# M10-4-20mA.net
KiCad netlist of a schematic drawn in Altium Designer
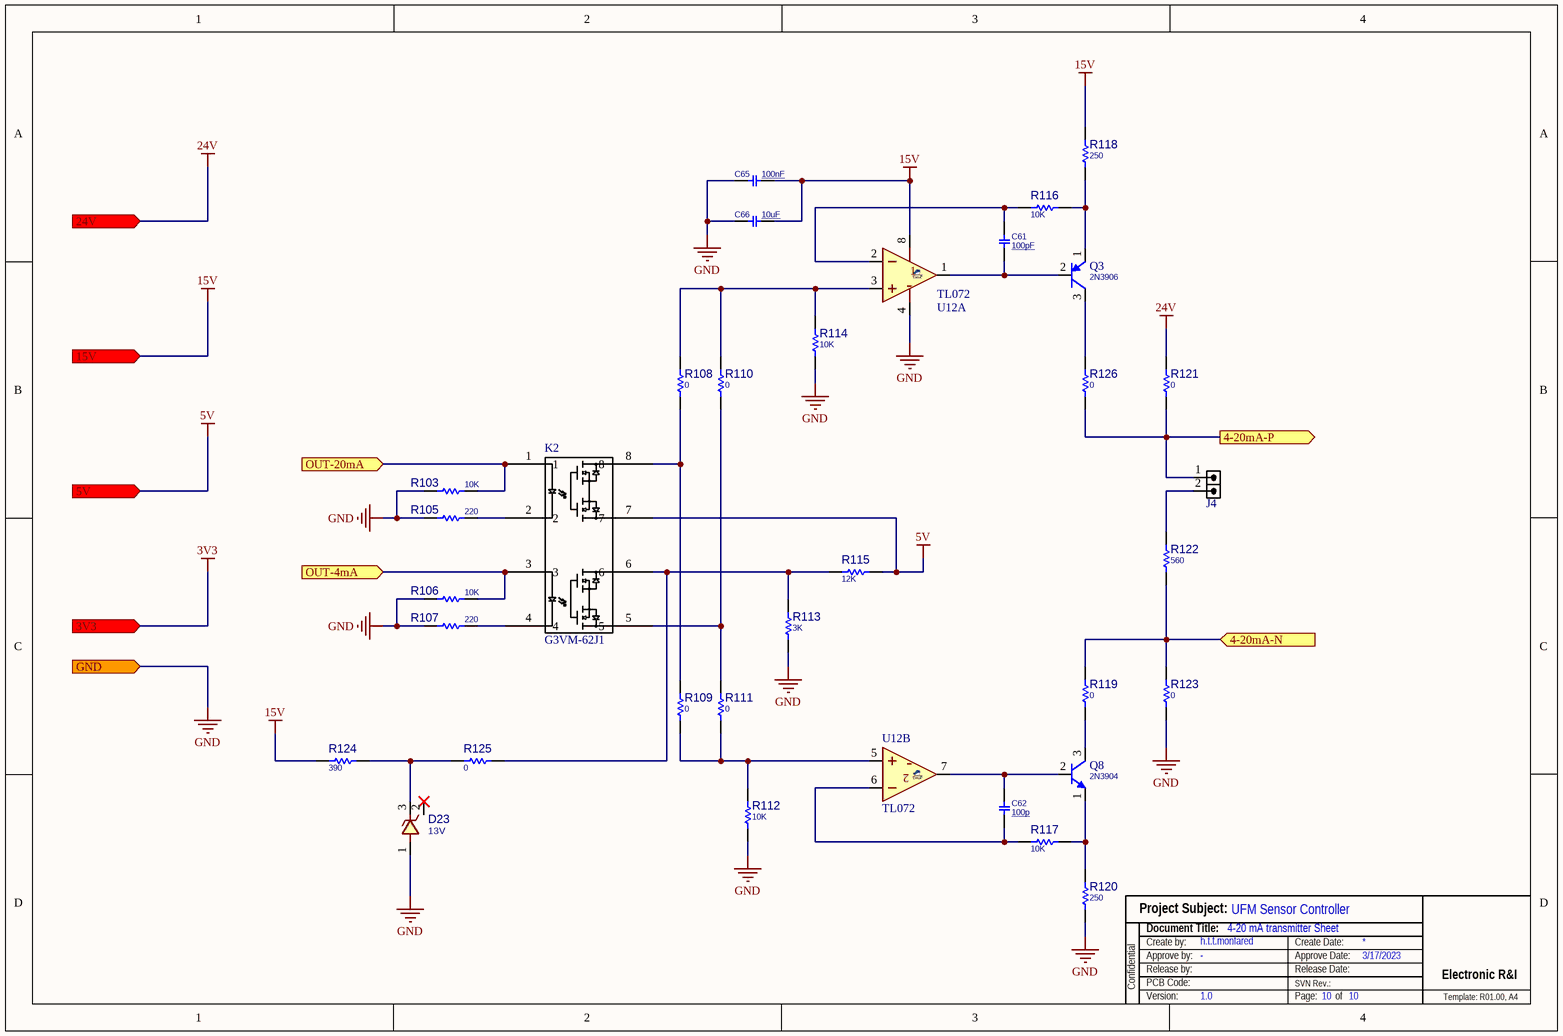
[diagram p0: M10-4-20mA.SchDoc]

(export (version "E")
  (design (tool "Eeschema 10.0.6"))
  (components
    (comp (ref "C61")
      (value "100pF")
      (footprint "C1206")
      (description "CAP, MLCC, 1nF, 50V, C0G, 10%, 0402")
      (fields (field (name "MANF_P#") "MANF_PART#") (field (name "MANF") "Murata"))
      (libsource (lib "passive_smd") (part "CAP_SMD_MLCC"))
    )
    (comp (ref "C62")
      (value "100p")
      (footprint "C1206")
      (description "CAP, MLCC, 1nF, 50V, C0G, 10%, 0402")
      (fields (field (name "MANF_P#") "MANF_PART#") (field (name "MANF") "Murata"))
      (libsource (lib "passive_smd") (part "CAP_SMD_MLCC"))
    )
    (comp (ref "C65")
      (value "100nF")
      (footprint "C1206")
      (description "CAP, MLCC, 1nF, 50V, C0G, 10%, 0402")
      (fields (field (name "MANF_P#") "MANF_PART#") (field (name "MANF") "Murata"))
      (libsource (lib "passive_smd") (part "CAP_SMD_MLCC"))
    )
    (comp (ref "C66")
      (value "10uF")
      (footprint "C1206")
      (description "CAP, MLCC, 1nF, 50V, C0G, 10%, 0402")
      (fields (field (name "MANF_P#") "MANF_PART#") (field (name "MANF") "Murata"))
      (libsource (lib "passive_smd") (part "CAP_SMD_MLCC"))
    )
    (comp (ref "D23")
      (value "13V")
      (footprint "SOT23_3")
      (description "DIODE, ZENER, 0.25W, 12.7V")
      (fields (field (name "MANF") "NXP") (field (name "MANF_P#") "BZX84-C12"))
      (libsource (lib "diode") (part "DIODE_SMD_ZENER_BZX84-C12"))
    )
    (comp (ref "J4")
      (value "HDRM2")
      (footprint "HDR_M_1X2")
      (description "CONN, HEADER, Male, pitch: 2.54mm, 2POS")
      (libsource (lib "conn_header_2.54_st") (part "HDR_M_1X2"))
    )
    (comp (ref "K2")
      (value "G3VM-62J1")
      (footprint "J-SOP8_OMR")
      (description "No Description Available")
      (libsource (lib "G3VM-62J1") (part "G3VM-62J1"))
    )
    (comp (ref "Q3")
      (value "2N3906")
      (footprint "TO92_3")
      (description "BJT, PNP, 40v, 0.6A, THD, TO92")
      (fields (field (name "MANF") "ST"))
      (libsource (lib "transistor_bjt") (part "PNP_2N3906_TO92"))
    )
    (comp (ref "Q8")
      (value "2N3904")
      (footprint "TO92_3")
      (description "BJT, NPN, 40v, 0.6A, THD, TO92")
      (fields (field (name "MANF") "ST"))
      (libsource (lib "transistor_bjt") (part "NPN_2N3904_TO92"))
    )
    (comp (ref "R103")
      (value "10K")
      (footprint "R1206")
      (description "RESISTOR, SMD")
      (libsource (lib "passive_smd") (part "RES_SMD"))
    )
    (comp (ref "R105")
      (value "220")
      (footprint "R1206")
      (description "RESISTOR, SMD")
      (libsource (lib "passive_smd") (part "RES_SMD"))
    )
    (comp (ref "R106")
      (value "10K")
      (footprint "R1206")
      (description "RESISTOR, SMD")
      (libsource (lib "passive_smd") (part "RES_SMD"))
    )
    (comp (ref "R107")
      (value "220")
      (footprint "R1206")
      (description "RESISTOR, SMD")
      (libsource (lib "passive_smd") (part "RES_SMD"))
    )
    (comp (ref "R108")
      (value "0")
      (footprint "R1206")
      (description "RESISTOR, SMD")
      (libsource (lib "passive_smd") (part "RES_SMD"))
    )
    (comp (ref "R109")
      (value "0")
      (footprint "R1206")
      (description "RESISTOR, SMD")
      (libsource (lib "passive_smd") (part "RES_SMD"))
    )
    (comp (ref "R110")
      (value "0")
      (footprint "R1206")
      (description "RESISTOR, SMD")
      (libsource (lib "passive_smd") (part "RES_SMD"))
    )
    (comp (ref "R111")
      (value "0")
      (footprint "R1206")
      (description "RESISTOR, SMD")
      (libsource (lib "passive_smd") (part "RES_SMD"))
    )
    (comp (ref "R112")
      (value "10K")
      (footprint "R1206")
      (description "RESISTOR, SMD")
      (libsource (lib "passive_smd") (part "RES_SMD"))
    )
    (comp (ref "R113")
      (value "3K")
      (footprint "R1206")
      (description "RESISTOR, SMD")
      (libsource (lib "passive_smd") (part "RES_SMD"))
    )
    (comp (ref "R114")
      (value "10K")
      (footprint "R1206")
      (description "RESISTOR, SMD")
      (libsource (lib "passive_smd") (part "RES_SMD"))
    )
    (comp (ref "R115")
      (value "12K")
      (footprint "R1206")
      (description "RESISTOR, SMD")
      (libsource (lib "passive_smd") (part "RES_SMD"))
    )
    (comp (ref "R116")
      (value "10K")
      (footprint "R1206")
      (description "RESISTOR, SMD")
      (libsource (lib "passive_smd") (part "RES_SMD"))
    )
    (comp (ref "R117")
      (value "10K")
      (footprint "R1206")
      (description "RESISTOR, SMD")
      (libsource (lib "passive_smd") (part "RES_SMD"))
    )
    (comp (ref "R118")
      (value "250")
      (footprint "R1206")
      (description "RESISTOR, SMD")
      (libsource (lib "passive_smd") (part "RES_SMD"))
    )
    (comp (ref "R119")
      (value "0")
      (footprint "R1206")
      (description "RESISTOR, SMD")
      (libsource (lib "passive_smd") (part "RES_SMD"))
    )
    (comp (ref "R120")
      (value "250")
      (footprint "R1206")
      (description "RESISTOR, SMD")
      (libsource (lib "passive_smd") (part "RES_SMD"))
    )
    (comp (ref "R121")
      (value "0")
      (footprint "R1206")
      (description "RESISTOR, SMD")
      (libsource (lib "passive_smd") (part "RES_SMD"))
    )
    (comp (ref "R122")
      (value "560")
      (footprint "R1210")
      (description "RESISTOR, SMD")
      (libsource (lib "passive_smd") (part "RES_SMD"))
    )
    (comp (ref "R123")
      (value "0")
      (footprint "R1206")
      (description "RESISTOR, SMD")
      (libsource (lib "passive_smd") (part "RES_SMD"))
    )
    (comp (ref "R124")
      (value "390")
      (footprint "R1206")
      (description "RESISTOR, SMD")
      (libsource (lib "passive_smd") (part "RES_SMD"))
    )
    (comp (ref "R125")
      (value "0")
      (footprint "R1206")
      (description "RESISTOR, SMD")
      (libsource (lib "passive_smd") (part "RES_SMD"))
    )
    (comp (ref "R126")
      (value "0")
      (footprint "R1206")
      (description "RESISTOR, SMD")
      (libsource (lib "passive_smd") (part "RES_SMD"))
    )
    (comp (ref "U12")
      (value "TL072")
      (footprint "SO_8")
      (description "AMP, Dual, Lo-Noise, JFET Input")
      (fields (field (name "MANF") "Texas Instruments") (field (name "MANF_P#") "TL072CDR, TL072IDR"))
      (libsource (lib "amp") (part "TL072_SOP8"))
    )
  )
  (nets
    (net (code "1") (name "/4-20mA-N") (class "Default")
      (node (ref "R119") (pin "2") (pinfunction "2_2") (pintype "passive"))
      (node (ref "R122") (pin "1") (pinfunction "1_1") (pintype "passive"))
      (node (ref "R123") (pin "2") (pinfunction "2_2") (pintype "passive"))
    )
    (net (code "2") (name "/4-20mA-P") (class "Default")
      (node (ref "J4") (pin "1") (pinfunction "1_1") (pintype "passive"))
      (node (ref "R121") (pin "1") (pinfunction "1_1") (pintype "passive"))
      (node (ref "R126") (pin "1") (pinfunction "1_1") (pintype "passive"))
    )
    (net (code "3") (name "/OUT-4mA") (class "Default")
      (node (ref "K2") (pin "3") (pinfunction "3_3") (pintype "passive"))
      (node (ref "R106") (pin "1") (pinfunction "1_1") (pintype "passive"))
    )
    (net (code "4") (name "/OUT-20mA") (class "Default")
      (node (ref "K2") (pin "1") (pinfunction "1_1") (pintype "passive"))
      (node (ref "R103") (pin "1") (pinfunction "1_1") (pintype "passive"))
    )
    (net (code "6") (name "5V") (class "Default")
      (node (ref "K2") (pin "7") (pinfunction "7_7") (pintype "passive"))
      (node (ref "R115") (pin "1") (pinfunction "1_1") (pintype "passive"))
    )
    (net (code "7") (name "15V") (class "Default")
      (node (ref "C65") (pin "2") (pinfunction "2_2") (pintype "passive"))
      (node (ref "C66") (pin "2") (pinfunction "2_2") (pintype "passive"))
      (node (ref "R118") (pin "2") (pinfunction "2_2") (pintype "passive"))
      (node (ref "R124") (pin "1") (pinfunction "1_1") (pintype "passive"))
      (node (ref "U12") (pin "8") (pinfunction "V+_8") (pintype "passive"))
    )
    (net (code "8") (name "24V") (class "Default")
      (node (ref "R121") (pin "2") (pinfunction "2_2") (pintype "passive"))
    )
    (net (code "9") (name "GND") (class "Default")
      (node (ref "C65") (pin "1") (pinfunction "1_1") (pintype "passive"))
      (node (ref "C66") (pin "1") (pinfunction "1_1") (pintype "passive"))
      (node (ref "D23") (pin "1") (pinfunction "1_1") (pintype "passive"))
      (node (ref "R103") (pin "2") (pinfunction "2_2") (pintype "passive"))
      (node (ref "R105") (pin "1") (pinfunction "1_1") (pintype "passive"))
      (node (ref "R106") (pin "2") (pinfunction "2_2") (pintype "passive"))
      (node (ref "R107") (pin "1") (pinfunction "1_1") (pintype "passive"))
      (node (ref "R112") (pin "1") (pinfunction "1_1") (pintype "passive"))
      (node (ref "R113") (pin "2") (pinfunction "2_2") (pintype "passive"))
      (node (ref "R114") (pin "1") (pinfunction "1_1") (pintype "passive"))
      (node (ref "R120") (pin "1") (pinfunction "1_1") (pintype "passive"))
      (node (ref "R123") (pin "1") (pinfunction "1_1") (pintype "passive"))
      (node (ref "U12") (pin "4") (pinfunction "V-_4") (pintype "passive"))
    )
    (net (code "10") (name "Net-(D23-Pad3)") (class "Default")
      (node (ref "D23") (pin "3") (pinfunction "3_3") (pintype "passive"))
      (node (ref "R124") (pin "2") (pinfunction "2_2") (pintype "passive"))
      (node (ref "R125") (pin "1") (pinfunction "1_1") (pintype "passive"))
    )
    (net (code "11") (name "Net-(J4-Pad2)") (class "Default")
      (node (ref "J4") (pin "2") (pinfunction "2_2") (pintype "passive"))
      (node (ref "R122") (pin "2") (pinfunction "2_2") (pintype "passive"))
    )
    (net (code "12") (name "Net-(K2-Pad2)") (class "Default")
      (node (ref "K2") (pin "2") (pinfunction "2_2") (pintype "passive"))
      (node (ref "R105") (pin "2") (pinfunction "2_2") (pintype "passive"))
    )
    (net (code "13") (name "Net-(K2-Pad4)") (class "Default")
      (node (ref "K2") (pin "4") (pinfunction "4_4") (pintype "passive"))
      (node (ref "R107") (pin "2") (pinfunction "2_2") (pintype "passive"))
    )
    (net (code "14") (name "Net-(K2-Pad5)") (class "Default")
      (node (ref "K2") (pin "5") (pinfunction "5_5") (pintype "passive"))
      (node (ref "R110") (pin "1") (pinfunction "1_1") (pintype "passive"))
      (node (ref "R111") (pin "2") (pinfunction "2_2") (pintype "passive"))
    )
    (net (code "15") (name "Net-(K2-Pad6)") (class "Default")
      (node (ref "K2") (pin "6") (pinfunction "6_6") (pintype "passive"))
      (node (ref "R113") (pin "1") (pinfunction "1_1") (pintype "passive"))
      (node (ref "R115") (pin "2") (pinfunction "2_2") (pintype "passive"))
      (node (ref "R125") (pin "2") (pinfunction "2_2") (pintype "passive"))
    )
    (net (code "16") (name "Net-(K2-Pad8)") (class "Default")
      (node (ref "K2") (pin "8") (pinfunction "8_8") (pintype "passive"))
      (node (ref "R108") (pin "1") (pinfunction "1_1") (pintype "passive"))
      (node (ref "R109") (pin "2") (pinfunction "2_2") (pintype "passive"))
    )
    (net (code "17") (name "Net-(Q3-B)") (class "Default")
      (node (ref "C61") (pin "1") (pinfunction "1_1") (pintype "passive"))
      (node (ref "Q3") (pin "2") (pinfunction "B_2") (pintype "passive"))
      (node (ref "U12") (pin "1") (pinfunction "OUT1_1") (pintype "passive"))
    )
    (net (code "18") (name "Net-(Q3-C)") (class "Default")
      (node (ref "Q3") (pin "3") (pinfunction "C_3") (pintype "passive"))
      (node (ref "R126") (pin "2") (pinfunction "2_2") (pintype "passive"))
    )
    (net (code "19") (name "Net-(Q3-E)") (class "Default")
      (node (ref "Q3") (pin "1") (pinfunction "E_1") (pintype "passive"))
      (node (ref "R116") (pin "2") (pinfunction "2_2") (pintype "passive"))
      (node (ref "R118") (pin "1") (pinfunction "1_1") (pintype "passive"))
    )
    (net (code "20") (name "Net-(Q8-B)") (class "Default")
      (node (ref "C62") (pin "2") (pinfunction "2_2") (pintype "passive"))
      (node (ref "Q8") (pin "2") (pinfunction "B_2") (pintype "passive"))
      (node (ref "U12") (pin "7") (pinfunction "OUT2_7") (pintype "passive"))
    )
    (net (code "21") (name "Net-(Q8-C)") (class "Default")
      (node (ref "Q8") (pin "3") (pinfunction "C_3") (pintype "passive"))
      (node (ref "R119") (pin "1") (pinfunction "1_1") (pintype "passive"))
    )
    (net (code "22") (name "Net-(Q8-E)") (class "Default")
      (node (ref "Q8") (pin "1") (pinfunction "E_1") (pintype "passive"))
      (node (ref "R117") (pin "1") (pinfunction "1_1") (pintype "passive"))
      (node (ref "R120") (pin "2") (pinfunction "2_2") (pintype "passive"))
    )
    (net (code "23") (name "Net-(U12A-IN1-)") (class "Default")
      (node (ref "C61") (pin "2") (pinfunction "2_2") (pintype "passive"))
      (node (ref "R116") (pin "1") (pinfunction "1_1") (pintype "passive"))
      (node (ref "U12") (pin "2") (pinfunction "IN1-_2") (pintype "passive"))
    )
    (net (code "24") (name "Net-(U12A-IN2+)") (class "Default")
      (node (ref "R108") (pin "2") (pinfunction "2_2") (pintype "passive"))
      (node (ref "R110") (pin "2") (pinfunction "2_2") (pintype "passive"))
      (node (ref "R114") (pin "2") (pinfunction "2_2") (pintype "passive"))
      (node (ref "U12") (pin "3") (pinfunction "IN2+_3") (pintype "passive"))
    )
    (net (code "25") (name "Net-(U12B-IN2+)") (class "Default")
      (node (ref "R109") (pin "1") (pinfunction "1_1") (pintype "passive"))
      (node (ref "R111") (pin "1") (pinfunction "1_1") (pintype "passive"))
      (node (ref "R112") (pin "2") (pinfunction "2_2") (pintype "passive"))
      (node (ref "U12") (pin "5") (pinfunction "IN2+_5") (pintype "passive"))
    )
    (net (code "26") (name "Net-(U12B-IN2-)") (class "Default")
      (node (ref "C62") (pin "1") (pinfunction "1_1") (pintype "passive"))
      (node (ref "R117") (pin "2") (pinfunction "2_2") (pintype "passive"))
      (node (ref "U12") (pin "6") (pinfunction "IN2-_6") (pintype "passive"))
    )
    (net (code "27") (name "unconnected-(D23-Pad2)") (class "Default")
      (node (ref "D23") (pin "2") (pinfunction "2_2") (pintype "passive+no_connect"))
    )
  )
)
